# Power_PCB_200.net
KiCad netlist of a schematic drawn in EAGLE
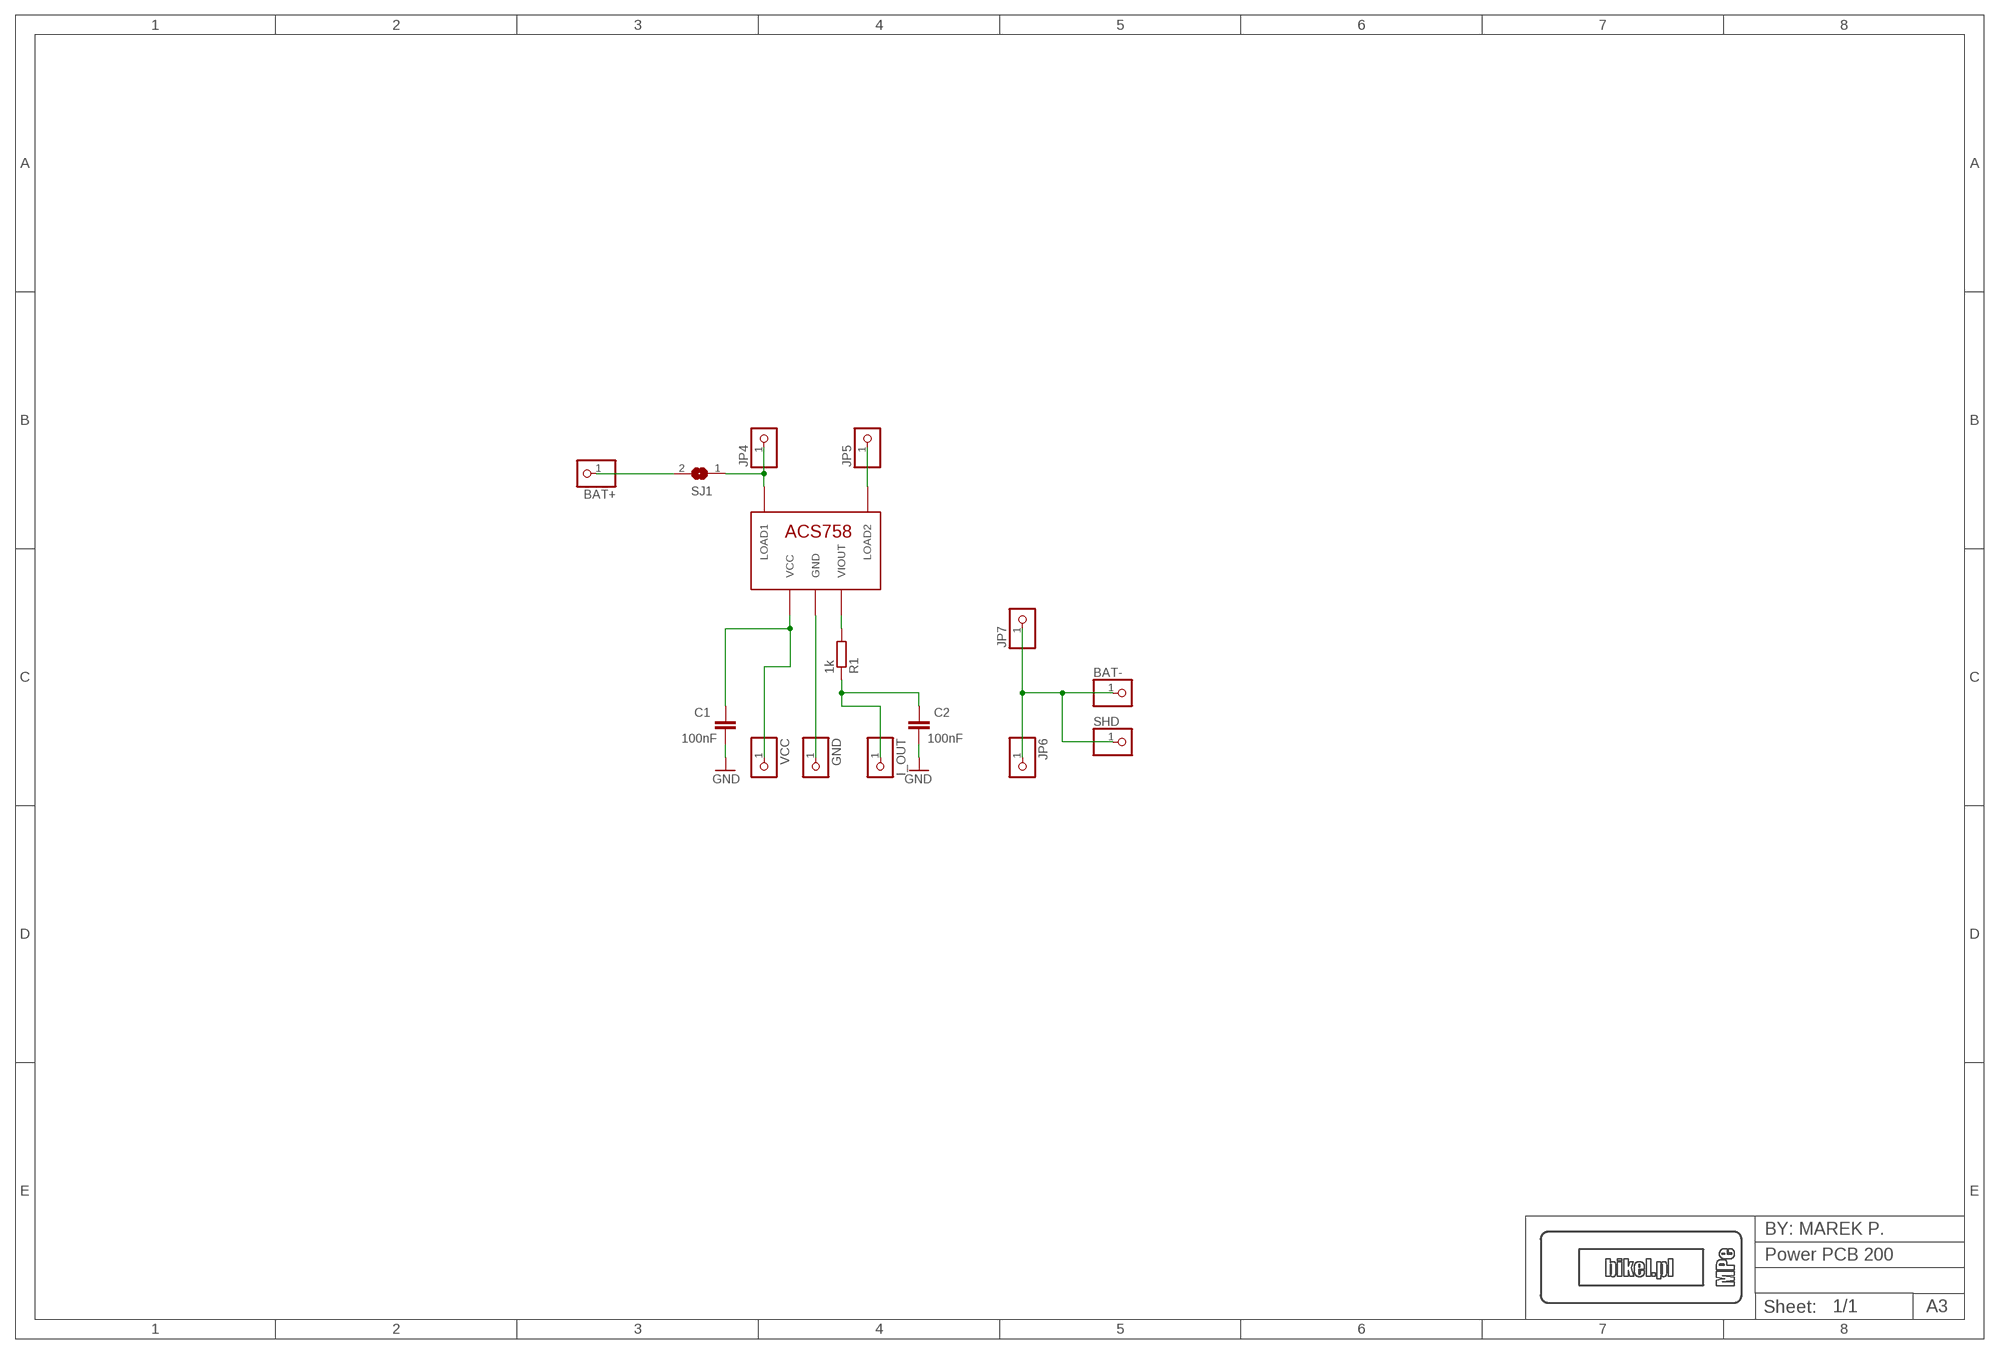
[diagram p0: schematic, sheet 1]

(export (version "E")
  (design (tool "Eeschema 10.0.6"))
  (components
    (comp (ref "ACS758_1")
      (value "ACS758")
      (footprint "eagle-import:ACS758-PFF")
      (libsource (lib "eagle-import") (part "ACS758"))
    )
    (comp (ref "BAT+")
      (value "PINHD-1X1")
      (footprint "eagle-import:1X01")
      (libsource (lib "eagle-import") (part "PINHD-1X1"))
    )
    (comp (ref "BAT-")
      (value "PINHD-1X1")
      (footprint "eagle-import:1X01")
      (libsource (lib "eagle-import") (part "PINHD-1X1"))
    )
    (comp (ref "C1")
      (value "100nF")
      (footprint "eagle-import:C0805")
      (libsource (lib "eagle-import") (part "C-EUC0805"))
    )
    (comp (ref "C2")
      (value "100nF")
      (footprint "eagle-import:C0805")
      (libsource (lib "eagle-import") (part "C-EUC0805"))
    )
    (comp (ref "GND")
      (value "PINHD-1X1")
      (footprint "eagle-import:1X01")
      (libsource (lib "eagle-import") (part "PINHD-1X1"))
    )
    (comp (ref "I_OUT")
      (value "PINHD-1X1")
      (footprint "eagle-import:1X01")
      (libsource (lib "eagle-import") (part "PINHD-1X1"))
    )
    (comp (ref "JP4")
      (value "PINHD-1X1")
      (footprint "eagle-import:1X01")
      (libsource (lib "eagle-import") (part "PINHD-1X1"))
    )
    (comp (ref "JP5")
      (value "PINHD-1X1")
      (footprint "eagle-import:1X01")
      (libsource (lib "eagle-import") (part "PINHD-1X1"))
    )
    (comp (ref "JP6")
      (value "PINHD-1X1")
      (footprint "eagle-import:1X01")
      (libsource (lib "eagle-import") (part "PINHD-1X1"))
    )
    (comp (ref "JP7")
      (value "PINHD-1X1")
      (footprint "eagle-import:1X01")
      (libsource (lib "eagle-import") (part "PINHD-1X1"))
    )
    (comp (ref "R1")
      (value "1k")
      (footprint "eagle-import:R0805")
      (libsource (lib "eagle-import") (part "R-EU_R0805"))
    )
    (comp (ref "SHD")
      (value "PINHD-1X1")
      (footprint "eagle-import:1X01")
      (libsource (lib "eagle-import") (part "PINHD-1X1"))
    )
    (comp (ref "SJ1") (value "SJ") (footprint "eagle-import:SJ") (libsource (lib "eagle-import") (part "SJ")))
    (comp (ref "VCC")
      (value "PINHD-1X1")
      (footprint "eagle-import:1X01")
      (libsource (lib "eagle-import") (part "PINHD-1X1"))
    )
  )
  (nets
    (net (code "1") (name "GND") (class "Default")
      (node (ref "ACS758_1") (pin "GND") (pinfunction "GND_GND") (pintype "bidirectional"))
      (node (ref "C1") (pin "2") (pinfunction "2_2") (pintype "passive"))
      (node (ref "C2") (pin "2") (pinfunction "2_2") (pintype "passive"))
      (node (ref "GND") (pin "1") (pinfunction "1_1") (pintype "passive"))
    )
    (net (code "2") (name "Net-(ACS758_1-PadLOAD1)") (class "Default")
      (node (ref "ACS758_1") (pin "LOAD1") (pinfunction "LOAD1_LOAD1") (pintype "bidirectional"))
      (node (ref "JP4") (pin "1") (pinfunction "1_1") (pintype "passive"))
      (node (ref "SJ1") (pin "1") (pinfunction "1_1") (pintype "passive"))
    )
    (net (code "3") (name "Net-(ACS758_1-PadLOAD2)") (class "Default")
      (node (ref "ACS758_1") (pin "LOAD2") (pinfunction "LOAD2_LOAD2") (pintype "bidirectional"))
      (node (ref "JP5") (pin "1") (pinfunction "1_1") (pintype "passive"))
    )
    (net (code "4") (name "Net-(ACS758_1-PadVCC)") (class "Default")
      (node (ref "ACS758_1") (pin "VCC") (pinfunction "VCC_VCC") (pintype "bidirectional"))
      (node (ref "C1") (pin "1") (pinfunction "1_1") (pintype "passive"))
      (node (ref "VCC") (pin "1") (pinfunction "1_1") (pintype "passive"))
    )
    (net (code "5") (name "Net-(ACS758_1-PadVIOUT)") (class "Default")
      (node (ref "ACS758_1") (pin "VIOUT") (pinfunction "VIOUT_VIOUT") (pintype "bidirectional"))
      (node (ref "R1") (pin "2") (pinfunction "2_2") (pintype "passive"))
    )
    (net (code "6") (name "Net-(BAT+-Pad1)") (class "Default")
      (node (ref "BAT+") (pin "1") (pinfunction "1_1") (pintype "passive"))
      (node (ref "SJ1") (pin "2") (pinfunction "2_2") (pintype "passive"))
    )
    (net (code "7") (name "Net-(BAT--Pad1)") (class "Default")
      (node (ref "BAT-") (pin "1") (pinfunction "1_1") (pintype "passive"))
      (node (ref "JP6") (pin "1") (pinfunction "1_1") (pintype "passive"))
      (node (ref "JP7") (pin "1") (pinfunction "1_1") (pintype "passive"))
      (node (ref "SHD") (pin "1") (pinfunction "1_1") (pintype "passive"))
    )
    (net (code "8") (name "Net-(C2-Pad1)") (class "Default")
      (node (ref "C2") (pin "1") (pinfunction "1_1") (pintype "passive"))
      (node (ref "I_OUT") (pin "1") (pinfunction "1_1") (pintype "passive"))
      (node (ref "R1") (pin "1") (pinfunction "1_1") (pintype "passive"))
    )
  )
)
